# Nano-RS485_RJ45-GW-v1_7.net
KiCad netlist of a schematic drawn in EAGLE
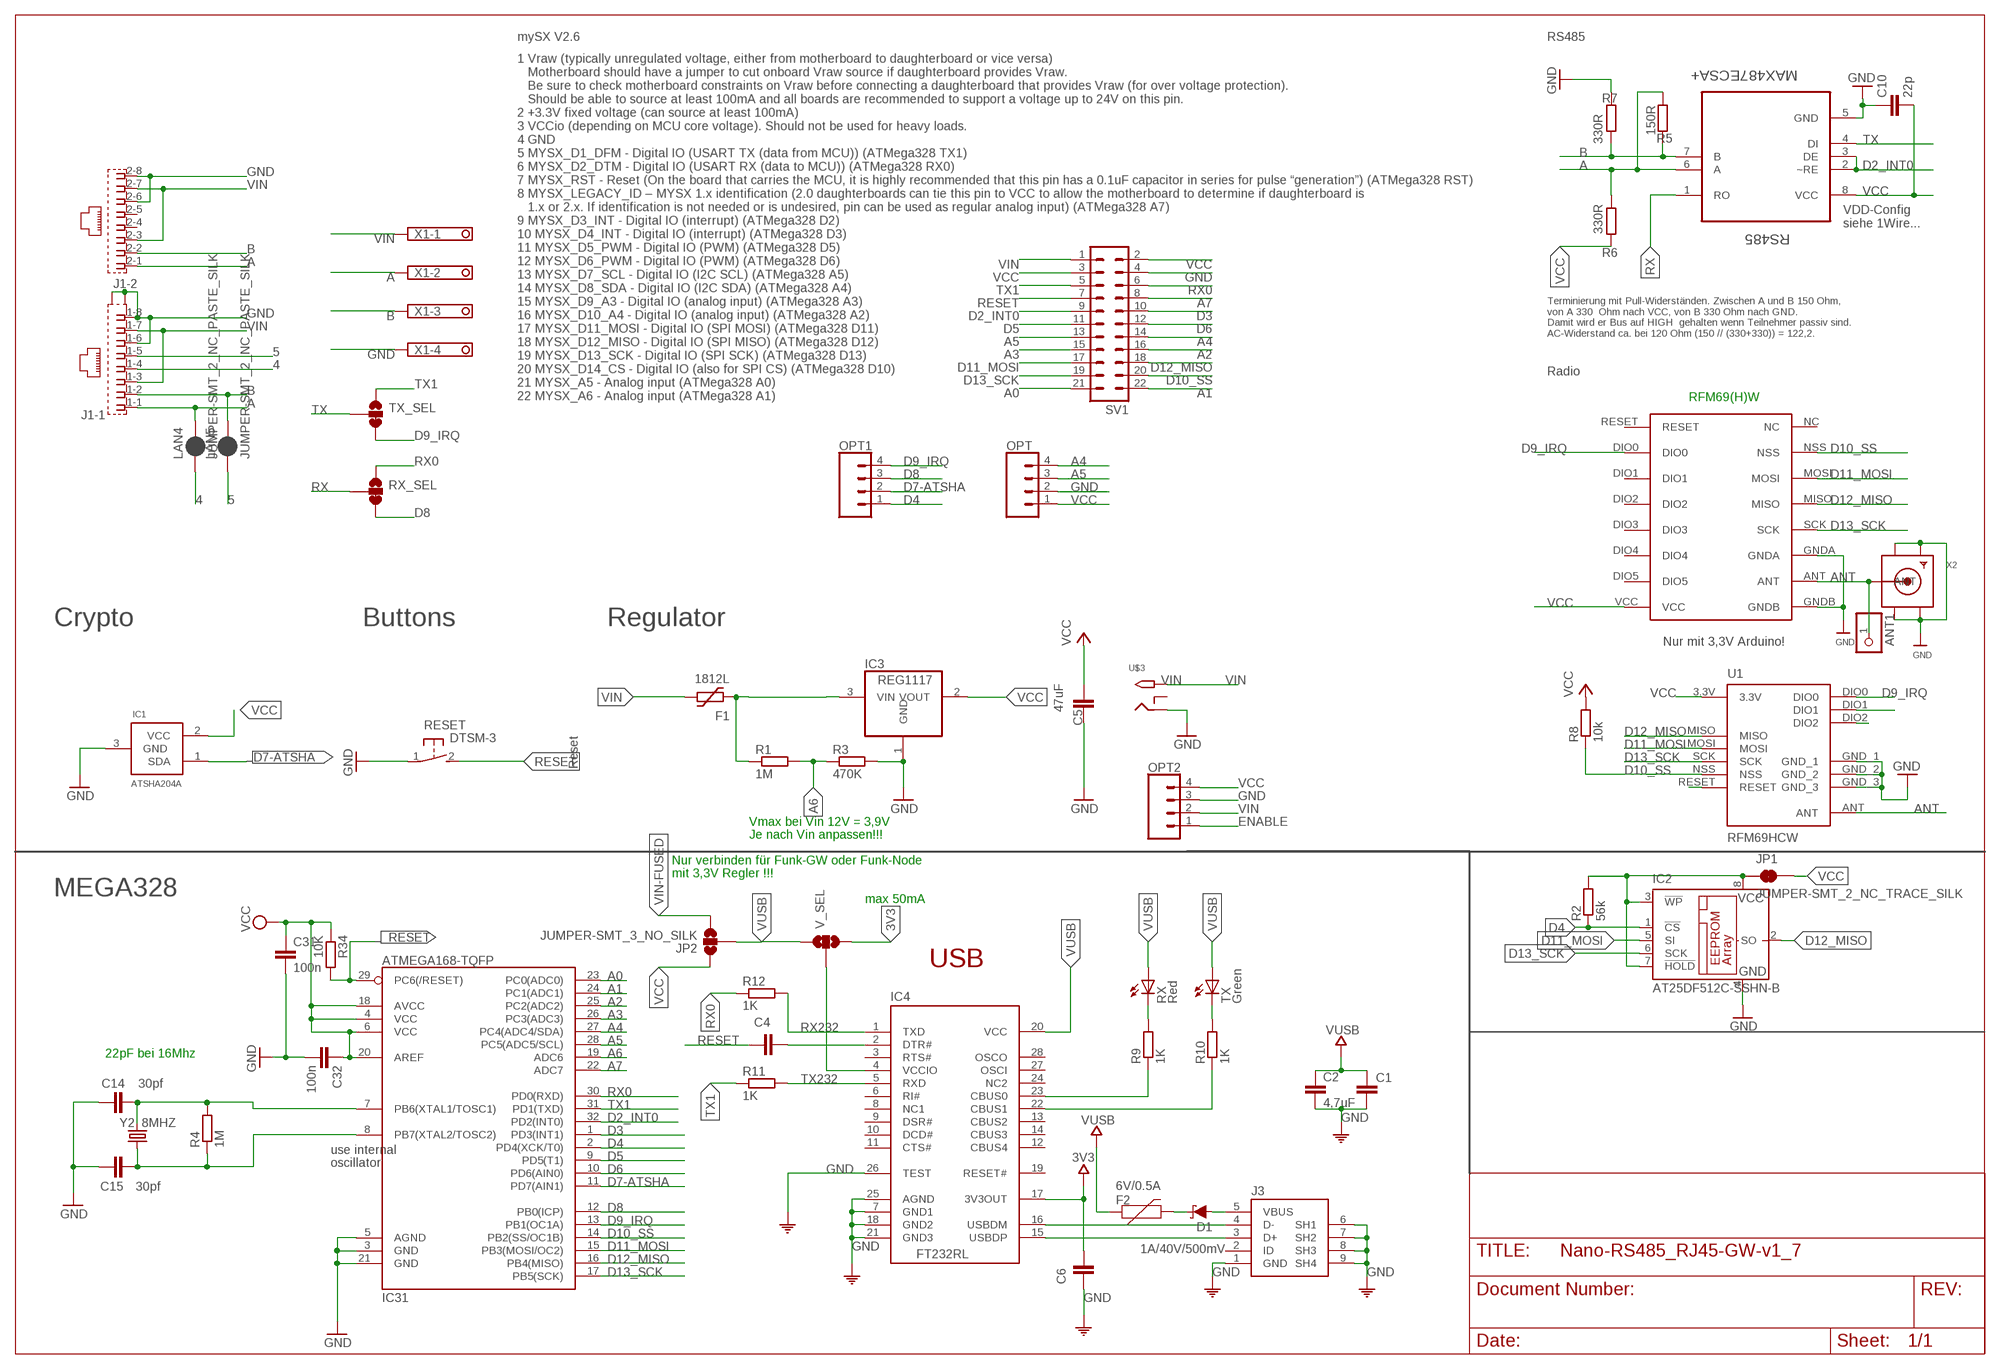
[diagram p0: schematic, sheet 1]

(export (version "E")
  (design (tool "Eeschema 10.0.6"))
  (components
    (comp (ref "ANT1")
      (value "PINHD-1X1")
      (footprint "eagle-import:1X01")
      (libsource (lib "eagle-import") (part "PINHD-1X1"))
    )
    (comp (ref "C1")
      (value "100nF")
      (footprint "eagle-import:C0805")
      (libsource (lib "eagle-import") (part "resistor@1_C-EUC0805"))
    )
    (comp (ref "C2")
      (value "4,7uF")
      (footprint "eagle-import:C1206")
      (libsource (lib "eagle-import") (part "resistor@1_C-EUC1206"))
    )
    (comp (ref "C4")
      (value "100nF")
      (footprint "eagle-import:C0805")
      (libsource (lib "eagle-import") (part "resistor@1_C-EUC0805"))
    )
    (comp (ref "C5")
      (value "47uF")
      (footprint "eagle-import:C1206")
      (libsource (lib "eagle-import") (part "resistor@1_C-EUC1206"))
    )
    (comp (ref "C6")
      (value "100nF")
      (footprint "eagle-import:C0805")
      (libsource (lib "eagle-import") (part "resistor@1_C-EUC0805"))
    )
    (comp (ref "C10")
      (value "22p")
      (footprint "eagle-import:C0805")
      (libsource (lib "eagle-import") (part "C-EUC0805"))
    )
    (comp (ref "C14")
      (value "30pf")
      (footprint "eagle-import:0805")
      (libsource (lib "eagle-import") (part "CAP0805"))
    )
    (comp (ref "C15")
      (value "30pf")
      (footprint "eagle-import:0805")
      (libsource (lib "eagle-import") (part "CAP0805"))
    )
    (comp (ref "C31")
      (value "100n")
      (footprint "eagle-import:C0805")
      (libsource (lib "eagle-import") (part "C-EUC0805"))
    )
    (comp (ref "C32")
      (value "100n")
      (footprint "eagle-import:C0805")
      (libsource (lib "eagle-import") (part "C-EUC0805"))
    )
    (comp (ref "D1")
      (value "1A/40V/500mV")
      (footprint "eagle-import:SMA-DIODE")
      (libsource (lib "eagle-import") (part "DIODE-SCHOTTKY-SS14"))
    )
    (comp (ref "F1")
      (value "1812L")
      (footprint "eagle-import:1812L")
      (libsource (lib "eagle-import") (part "1812L"))
    )
    (comp (ref "F2")
      (value "6V/0.5A")
      (footprint "eagle-import:1206")
      (libsource (lib "eagle-import") (part "PPTC_HALF-AMP"))
    )
    (comp (ref "IC1")
      (value "ATSHA204A")
      (footprint "eagle-import:SOT23")
      (libsource (lib "eagle-import") (part "ATSHA204A"))
    )
    (comp (ref "IC2")
      (value "AT25DF512C-SSHN-B")
      (footprint "eagle-import:SO-08")
      (fields (field (name "MF") "MICROCHIP") (field (name "MPN") "25AA080/SN"))
      (libsource (lib "eagle-import") (part "25SNAA080"))
    )
    (comp (ref "IC3")
      (value "REG1117")
      (footprint "eagle-import:SOT223")
      (libsource (lib "eagle-import") (part "REG1117"))
    )
    (comp (ref "IC4")
      (value "FT232RL")
      (footprint "eagle-import:SSOP28")
      (libsource (lib "eagle-import") (part "0226_FT232RL"))
    )
    (comp (ref "IC31")
      (value "ATMEGA168-TQFP")
      (footprint "eagle-import:TQFP32-08")
      (libsource (lib "eagle-import") (part "ATMEGA168-TQFP"))
    )
    (comp (ref "J1")
      (value "RJ45_2X_NARROW_SHILDPINS_NOCASE")
      (footprint "eagle-import:RJ45_2X_NARROW_SHILDPINS_NOCASE")
      (libsource (lib "eagle-import") (part "RJ45_2X_NARROW_SHILDPINS_NOCASE"))
    )
    (comp (ref "J3")
      (value "0219_14850")
      (footprint "eagle-import:USB-MINI-B_2")
      (fields (field (name "PART_NUMBER") "14850"))
      (libsource (lib "eagle-import") (part "0219_14850"))
    )
    (comp (ref "JP1")
      (value "JUMPER-SMT_2_NC_TRACE_SILK")
      (footprint "eagle-import:SMT-JUMPER_2_NC_TRACE_SILK")
      (libsource (lib "eagle-import") (part "JUMPER-SMT_2_NC_TRACE_SILK"))
    )
    (comp (ref "JP2")
      (value "JUMPER-SMT_3_NO_SILK")
      (footprint "eagle-import:SMT-JUMPER_3_NO_SILK")
      (libsource (lib "eagle-import") (part "JUMPER-SMT_3_NO_SILK"))
    )
    (comp (ref "LAN4")
      (value "JUMPER-SMT_2_NC_PASTE_SILK")
      (footprint "eagle-import:SMT-JUMPER_2_NC_PASTE_SILK")
      (libsource (lib "eagle-import") (part "JUMPER-SMT_2_NC_PASTE_SILK"))
    )
    (comp (ref "LAN5")
      (value "JUMPER-SMT_2_NC_PASTE_SILK")
      (footprint "eagle-import:SMT-JUMPER_2_NC_PASTE_SILK")
      (libsource (lib "eagle-import") (part "JUMPER-SMT_2_NC_PASTE_SILK"))
    )
    (comp (ref "OPT")
      (value "CONN_04")
      (footprint "eagle-import:1X04")
      (libsource (lib "eagle-import") (part "CONN_04"))
    )
    (comp (ref "OPT1")
      (value "CONN_04")
      (footprint "eagle-import:1X04")
      (libsource (lib "eagle-import") (part "CONN_04"))
    )
    (comp (ref "OPT2")
      (value "CONN_04")
      (footprint "eagle-import:1X04")
      (libsource (lib "eagle-import") (part "CONN_04"))
    )
    (comp (ref "R1")
      (value "1M")
      (footprint "eagle-import:M0805")
      (libsource (lib "eagle-import") (part "R-EU_M0805"))
    )
    (comp (ref "R2")
      (value "56k")
      (footprint "eagle-import:M0805")
      (libsource (lib "eagle-import") (part "resistor_R-EU_M0805"))
    )
    (comp (ref "R3")
      (value "470K")
      (footprint "eagle-import:R0805")
      (libsource (lib "eagle-import") (part "R-EU_R0805"))
    )
    (comp (ref "R4")
      (value "1M")
      (footprint "eagle-import:M0805")
      (libsource (lib "eagle-import") (part "R-EU_M0805"))
    )
    (comp (ref "R5")
      (value "150R")
      (footprint "eagle-import:R0805")
      (libsource (lib "eagle-import") (part "R-EU_R0805"))
    )
    (comp (ref "R6")
      (value "330R")
      (footprint "eagle-import:R0805")
      (libsource (lib "eagle-import") (part "R-EU_R0805"))
    )
    (comp (ref "R7")
      (value "330R")
      (footprint "eagle-import:R0805")
      (libsource (lib "eagle-import") (part "R-EU_R0805"))
    )
    (comp (ref "R8")
      (value "10k")
      (footprint "eagle-import:M0805")
      (libsource (lib "eagle-import") (part "R-EU_M0805"))
    )
    (comp (ref "R9")
      (value "1K")
      (footprint "eagle-import:R0805")
      (libsource (lib "eagle-import") (part "resistor@1_R-EU_R0805"))
    )
    (comp (ref "R10")
      (value "1K")
      (footprint "eagle-import:R0805")
      (libsource (lib "eagle-import") (part "resistor@1_R-EU_R0805"))
    )
    (comp (ref "R11")
      (value "1K")
      (footprint "eagle-import:R0805")
      (libsource (lib "eagle-import") (part "resistor@1_R-EU_R0805"))
    )
    (comp (ref "R12")
      (value "1K")
      (footprint "eagle-import:R0805")
      (libsource (lib "eagle-import") (part "resistor@1_R-EU_R0805"))
    )
    (comp (ref "R34")
      (value "10K")
      (footprint "eagle-import:R0805")
      (libsource (lib "eagle-import") (part "R-EU_R0805"))
    )
    (comp (ref "RESET")
      (value "DTSM-3")
      (footprint "eagle-import:DTSM-3")
      (libsource (lib "eagle-import") (part "DTSM-3"))
    )
    (comp (ref "RFM69W")
      (value "RFM69HW")
      (footprint "eagle-import:RFM")
      (libsource (lib "eagle-import") (part "RFM69HW"))
    )
    (comp (ref "RS485")
      (value "MAX487ECSA+")
      (footprint "eagle-import:SOIC127P600X175-8N")
      (libsource (lib "eagle-import") (part "MAX487ECSA+"))
    )
    (comp (ref "RX")
      (value "Red")
      (footprint "eagle-import:CHIPLED_0805")
      (fields (field (name "PART_NUMBER") "KTP-2012SURCK"))
      (libsource (lib "eagle-import") (part "0181_KTP-2012SURCK"))
    )
    (comp (ref "RX_SEL")
      (value "JUMPER-SMT_3_1-NC_TRACE_SILK")
      (footprint "eagle-import:SMT-JUMPER_3_1-NC_TRACE_SILK")
      (libsource (lib "eagle-import") (part "JUMPER-SMT_3_1-NC_TRACE_SILK"))
    )
    (comp (ref "SV1")
      (value "MA11-2")
      (footprint "eagle-import:MA11-2")
      (libsource (lib "eagle-import") (part "MA11-2"))
    )
    (comp (ref "TX")
      (value "Green")
      (footprint "eagle-import:CHIPLED_0805")
      (fields (field (name "PART_NUMBER") "KPT-2012SGC"))
      (libsource (lib "eagle-import") (part "0043_KPT-2012SGC"))
    )
    (comp (ref "TX_SEL")
      (value "JUMPER-SMT_3_1-NC_TRACE_SILK")
      (footprint "eagle-import:SMT-JUMPER_3_1-NC_TRACE_SILK")
      (libsource (lib "eagle-import") (part "JUMPER-SMT_3_1-NC_TRACE_SILK"))
    )
    (comp (ref "U$3")
      (value "2.1MMJACKTHM")
      (footprint "eagle-import:PJ-102A")
      (libsource (lib "eagle-import") (part "2.1MMJACKTHM"))
    )
    (comp (ref "U1")
      (value "RFM69HCW")
      (footprint "eagle-import:RFM69HCW-XXXS2")
      (libsource (lib "eagle-import") (part "RFM69HCW"))
    )
    (comp (ref "V_SEL")
      (value "JUMPER-SMT_3_NO_SILK")
      (footprint "eagle-import:SMT-JUMPER_3_NO_SILK")
      (libsource (lib "eagle-import") (part "JUMPER-SMT_3_NO_SILK"))
    )
    (comp (ref "X1")
      (value "1751264")
      (footprint "eagle-import:1751264")
      (libsource (lib "eagle-import") (part "1751264"))
    )
    (comp (ref "X2")
      (value "SMACONNECTOR_EDGE")
      (footprint "eagle-import:SMA_EDGELAUNCH")
      (libsource (lib "eagle-import") (part "SMACONNECTOR_EDGE"))
    )
    (comp (ref "Y2")
      (value "8MHZ")
      (footprint "eagle-import:CRYSTAL-TXC-7A")
      (libsource (lib "eagle-import") (part "CRYSTALTXC-7A"))
    )
  )
  (nets
    (net (code "1") (name "/4") (class "Default")
      (node (ref "J1") (pin "1-4") (pinfunction "4_1-4") (pintype "passive"))
      (node (ref "LAN4") (pin "1") (pinfunction "1_1") (pintype "passive"))
    )
    (net (code "2") (name "/5") (class "Default")
      (node (ref "J1") (pin "1-5") (pinfunction "5_1-5") (pintype "passive"))
      (node (ref "LAN5") (pin "1") (pinfunction "1_1") (pintype "passive"))
    )
    (net (code "3") (name "/A") (class "Default")
      (node (ref "J1") (pin "1-1") (pinfunction "1_1-1") (pintype "passive"))
      (node (ref "J1") (pin "2-1") (pinfunction "1_2-1") (pintype "passive"))
      (node (ref "LAN4") (pin "2") (pinfunction "2_2") (pintype "passive"))
      (node (ref "R5") (pin "1") (pinfunction "1_1") (pintype "passive"))
      (node (ref "R6") (pin "2") (pinfunction "2_2") (pintype "passive"))
      (node (ref "RS485") (pin "6") (pinfunction "A_6") (pintype "bidirectional"))
      (node (ref "X1") (pin "2") (pinfunction "K_2") (pintype "passive"))
    )
    (net (code "4") (name "/A0") (class "Default")
      (node (ref "IC31") (pin "23") (pinfunction "PC0(ADC0)_23") (pintype "bidirectional"))
      (node (ref "SV1") (pin "21") (pinfunction "21_21") (pintype "passive"))
    )
    (net (code "5") (name "/A1") (class "Default")
      (node (ref "IC31") (pin "24") (pinfunction "PC1(ADC1)_24") (pintype "bidirectional"))
      (node (ref "SV1") (pin "22") (pinfunction "22_22") (pintype "passive"))
    )
    (net (code "6") (name "/A2") (class "Default")
      (node (ref "IC31") (pin "25") (pinfunction "PC2(ADC2)_25") (pintype "bidirectional"))
      (node (ref "SV1") (pin "16") (pinfunction "16_16") (pintype "passive"))
    )
    (net (code "7") (name "/A3") (class "Default")
      (node (ref "IC31") (pin "26") (pinfunction "PC3(ADC3)_26") (pintype "bidirectional"))
      (node (ref "SV1") (pin "15") (pinfunction "15_15") (pintype "passive"))
    )
    (net (code "8") (name "/A4") (class "Default")
      (node (ref "IC31") (pin "27") (pinfunction "PC4(ADC4/SDA)_27") (pintype "bidirectional"))
      (node (ref "OPT") (pin "4") (pinfunction "4_4") (pintype "passive"))
      (node (ref "SV1") (pin "14") (pinfunction "14_14") (pintype "passive"))
    )
    (net (code "9") (name "/A5") (class "Default")
      (node (ref "IC31") (pin "28") (pinfunction "PC5(ADC5/SCL)_28") (pintype "bidirectional"))
      (node (ref "OPT") (pin "3") (pinfunction "3_3") (pintype "passive"))
      (node (ref "SV1") (pin "13") (pinfunction "13_13") (pintype "passive"))
    )
    (net (code "10") (name "/A7") (class "Default")
      (node (ref "IC31") (pin "22") (pinfunction "ADC7_22") (pintype "bidirectional"))
      (node (ref "SV1") (pin "8") (pinfunction "8_8") (pintype "passive"))
    )
    (net (code "11") (name "/ANT") (class "Default")
      (node (ref "ANT1") (pin "1") (pinfunction "1_1") (pintype "passive"))
      (node (ref "RFM69W") (pin "ANT") (pinfunction "ANT_ANT") (pintype "bidirectional"))
      (node (ref "U1") (pin "ANT") (pinfunction "ANT_ANT") (pintype "passive"))
      (node (ref "X2") (pin "P") (pinfunction "ANT_P") (pintype "bidirectional"))
    )
    (net (code "12") (name "/B") (class "Default")
      (node (ref "J1") (pin "1-2") (pinfunction "2_1-2") (pintype "passive"))
      (node (ref "J1") (pin "2-2") (pinfunction "2_2-2") (pintype "passive"))
      (node (ref "LAN5") (pin "2") (pinfunction "2_2") (pintype "passive"))
      (node (ref "R5") (pin "2") (pinfunction "2_2") (pintype "passive"))
      (node (ref "R7") (pin "1") (pinfunction "1_1") (pintype "passive"))
      (node (ref "RS485") (pin "7") (pinfunction "B_7") (pintype "bidirectional"))
      (node (ref "X1") (pin "3") (pinfunction "K_3") (pintype "passive"))
    )
    (net (code "13") (name "/D2_INT0") (class "Default")
      (node (ref "IC31") (pin "32") (pinfunction "PD2(INT0)_32") (pintype "bidirectional"))
      (node (ref "RS485") (pin "2") (pinfunction "~{RE}_2") (pintype "input"))
      (node (ref "RS485") (pin "3") (pinfunction "DE_3") (pintype "input"))
      (node (ref "SV1") (pin "9") (pinfunction "9_9") (pintype "passive"))
    )
    (net (code "14") (name "/D3") (class "Default")
      (node (ref "IC31") (pin "1") (pinfunction "PD3(INT1)_1") (pintype "bidirectional"))
      (node (ref "SV1") (pin "10") (pinfunction "10_10") (pintype "passive"))
    )
    (net (code "15") (name "/D5") (class "Default")
      (node (ref "IC31") (pin "9") (pinfunction "PD5(T1)_9") (pintype "bidirectional"))
      (node (ref "SV1") (pin "11") (pinfunction "11_11") (pintype "passive"))
    )
    (net (code "16") (name "/D6") (class "Default")
      (node (ref "IC31") (pin "10") (pinfunction "PD6(AIN0)_10") (pintype "bidirectional"))
      (node (ref "SV1") (pin "12") (pinfunction "12_12") (pintype "passive"))
    )
    (net (code "17") (name "/D7-ATSHA") (class "Default")
      (node (ref "IC1") (pin "1") (pinfunction "SDA_1") (pintype "bidirectional"))
      (node (ref "IC31") (pin "11") (pinfunction "PD7(AIN1)_11") (pintype "bidirectional"))
      (node (ref "OPT1") (pin "2") (pinfunction "2_2") (pintype "passive"))
    )
    (net (code "18") (name "/D8") (class "Default")
      (node (ref "IC31") (pin "12") (pinfunction "PB0(ICP)_12") (pintype "bidirectional"))
      (node (ref "OPT1") (pin "3") (pinfunction "3_3") (pintype "passive"))
      (node (ref "RX_SEL") (pin "3") (pinfunction "3_3") (pintype "passive"))
    )
    (net (code "19") (name "/D9_IRQ") (class "Default")
      (node (ref "IC31") (pin "13") (pinfunction "PB1(OC1A)_13") (pintype "bidirectional"))
      (node (ref "OPT1") (pin "4") (pinfunction "4_4") (pintype "passive"))
      (node (ref "RFM69W") (pin "DIO0") (pinfunction "DIO0_DIO0") (pintype "bidirectional"))
      (node (ref "TX_SEL") (pin "3") (pinfunction "3_3") (pintype "passive"))
      (node (ref "U1") (pin "DIO0") (pinfunction "DIO0_DIO0") (pintype "bidirectional"))
    )
    (net (code "20") (name "/D10_SS") (class "Default")
      (node (ref "IC31") (pin "14") (pinfunction "PB2(SS/OC1B)_14") (pintype "bidirectional"))
      (node (ref "R8") (pin "1") (pinfunction "1_1") (pintype "passive"))
      (node (ref "RFM69W") (pin "NSS") (pinfunction "NSS_NSS") (pintype "bidirectional"))
      (node (ref "SV1") (pin "20") (pinfunction "20_20") (pintype "passive"))
      (node (ref "U1") (pin "NSS") (pinfunction "NSS_NSS") (pintype "input"))
    )
    (net (code "21") (name "/ENABLE") (class "Default")
      (node (ref "OPT2") (pin "1") (pinfunction "1_1") (pintype "passive"))
    )
    (net (code "22") (name "/RX232") (class "Default")
      (node (ref "IC4") (pin "1") (pinfunction "TXD_1") (pintype "output"))
      (node (ref "R12") (pin "2") (pinfunction "2_2") (pintype "passive"))
    )
    (net (code "23") (name "/TX") (class "Default")
      (node (ref "RS485") (pin "4") (pinfunction "DI_4") (pintype "input"))
      (node (ref "TX_SEL") (pin "2") (pinfunction "2_2") (pintype "passive"))
    )
    (net (code "24") (name "/TX232") (class "Default")
      (node (ref "IC4") (pin "5") (pinfunction "RXD_5") (pintype "input"))
      (node (ref "R11") (pin "2") (pinfunction "2_2") (pintype "passive"))
    )
    (net (code "25") (name "3V3") (class "Default")
      (node (ref "C6") (pin "2") (pinfunction "2_2") (pintype "passive"))
      (node (ref "IC4") (pin "17") (pinfunction "3V3OUT_17") (pintype "power_in"))
      (node (ref "V_SEL") (pin "3") (pinfunction "3_3") (pintype "passive"))
    )
    (net (code "26") (name "A6") (class "Default")
      (node (ref "IC31") (pin "19") (pinfunction "ADC6_19") (pintype "bidirectional"))
      (node (ref "R1") (pin "2") (pinfunction "2_2") (pintype "passive"))
      (node (ref "R3") (pin "1") (pinfunction "1_1") (pintype "passive"))
    )
    (net (code "27") (name "COM") (class "Default")
      (node (ref "C1") (pin "2") (pinfunction "2_2") (pintype "passive"))
      (node (ref "C10") (pin "1") (pinfunction "1_1") (pintype "passive"))
      (node (ref "C14") (pin "1") (pinfunction "1_1") (pintype "passive"))
      (node (ref "C15") (pin "1") (pinfunction "1_1") (pintype "passive"))
      (node (ref "C2") (pin "2") (pinfunction "2_2") (pintype "passive"))
      (node (ref "C31") (pin "2") (pinfunction "2_2") (pintype "passive"))
      (node (ref "C32") (pin "2") (pinfunction "2_2") (pintype "passive"))
      (node (ref "C5") (pin "1") (pinfunction "1_1") (pintype "passive"))
      (node (ref "C6") (pin "1") (pinfunction "1_1") (pintype "passive"))
      (node (ref "IC1") (pin "3") (pinfunction "GND_3") (pintype "bidirectional"))
      (node (ref "IC2") (pin "4") (pinfunction "GND_4") (pintype "power_in"))
      (node (ref "IC3") (pin "1") (pinfunction "GND_1") (pintype "power_in"))
      (node (ref "IC31") (pin "21") (pinfunction "GND_21") (pintype "bidirectional"))
      (node (ref "IC31") (pin "3") (pinfunction "GND_3") (pintype "bidirectional"))
      (node (ref "IC31") (pin "5") (pinfunction "AGND_5") (pintype "bidirectional"))
      (node (ref "IC4") (pin "18") (pinfunction "GND2_18") (pintype "power_in"))
      (node (ref "IC4") (pin "21") (pinfunction "GND3_21") (pintype "power_in"))
      (node (ref "IC4") (pin "25") (pinfunction "AGND_25") (pintype "power_in"))
      (node (ref "IC4") (pin "26") (pinfunction "TEST_26") (pintype "bidirectional"))
      (node (ref "IC4") (pin "7") (pinfunction "GND1_7") (pintype "power_in"))
      (node (ref "J1") (pin "1-6") (pinfunction "6_1-6") (pintype "passive"))
      (node (ref "J1") (pin "1-8") (pinfunction "8_1-8") (pintype "passive"))
      (node (ref "J1") (pin "2-6") (pinfunction "6_2-6") (pintype "passive"))
      (node (ref "J1") (pin "2-8") (pinfunction "8_2-8") (pintype "passive"))
      (node (ref "J1") (pin "G1") (pinfunction "S1_G1") (pintype "passive"))
      (node (ref "J1") (pin "G3") (pinfunction "S2_G3") (pintype "passive"))
      (node (ref "J3") (pin "1") (pinfunction "GND_1") (pintype "passive"))
      (node (ref "J3") (pin "6") (pinfunction "SH1_6") (pintype "passive"))
      (node (ref "J3") (pin "7") (pinfunction "SH2_7") (pintype "passive"))
      (node (ref "J3") (pin "8") (pinfunction "SH3_8") (pintype "passive"))
      (node (ref "J3") (pin "9") (pinfunction "SH4_9") (pintype "passive"))
      (node (ref "OPT") (pin "2") (pinfunction "2_2") (pintype "passive"))
      (node (ref "OPT2") (pin "3") (pinfunction "3_3") (pintype "passive"))
      (node (ref "R3") (pin "2") (pinfunction "2_2") (pintype "passive"))
      (node (ref "R7") (pin "2") (pinfunction "2_2") (pintype "passive"))
      (node (ref "RESET") (pin "1") (pinfunction "1_1") (pintype "passive"))
      (node (ref "RFM69W") (pin "GNDA") (pinfunction "GNDA_GNDA") (pintype "bidirectional"))
      (node (ref "RFM69W") (pin "GNDB") (pinfunction "GNDB_GNDB") (pintype "bidirectional"))
      (node (ref "RS485") (pin "5") (pinfunction "GND_5") (pintype "passive"))
      (node (ref "SV1") (pin "4") (pinfunction "4_4") (pintype "passive"))
      (node (ref "U$3") (pin "RING") (pinfunction "RING_RING") (pintype "bidirectional"))
      (node (ref "U1") (pin "GND_1") (pinfunction "GND_1_GND_1") (pintype "power_in"))
      (node (ref "U1") (pin "GND_2") (pinfunction "GND_2_GND_2") (pintype "power_in"))
      (node (ref "U1") (pin "GND_3") (pinfunction "GND_3_GND_3") (pintype "power_in"))
      (node (ref "X1") (pin "4") (pinfunction "K_4") (pintype "passive"))
      (node (ref "X2") (pin "GND@1") (pinfunction "GND4_GND@1") (pintype "power_in"))
      (node (ref "X2") (pin "GND@2") (pinfunction "GND3_GND@2") (pintype "power_in"))
      (node (ref "X2") (pin "GND@3") (pinfunction "GND2_GND@3") (pintype "power_in"))
      (node (ref "X2") (pin "GND@4") (pinfunction "GND1_GND@4") (pintype "power_in"))
    )
    (net (code "28") (name "D4") (class "Default")
      (node (ref "IC2") (pin "1") (pinfunction "~{CS}_1") (pintype "input"))
      (node (ref "IC31") (pin "2") (pinfunction "PD4(XCK/T0)_2") (pintype "bidirectional"))
      (node (ref "OPT1") (pin "1") (pinfunction "1_1") (pintype "passive"))
      (node (ref "R2") (pin "1") (pinfunction "1_1") (pintype "passive"))
    )
    (net (code "29") (name "D11_MOSI") (class "Default")
      (node (ref "IC2") (pin "5") (pinfunction "SI_5") (pintype "input"))
      (node (ref "IC31") (pin "15") (pinfunction "PB3(MOSI/OC2)_15") (pintype "bidirectional"))
      (node (ref "RFM69W") (pin "MOSI") (pinfunction "MOSI_MOSI") (pintype "bidirectional"))
      (node (ref "SV1") (pin "17") (pinfunction "17_17") (pintype "passive"))
      (node (ref "U1") (pin "MOSI") (pinfunction "MOSI_MOSI") (pintype "input"))
    )
    (net (code "30") (name "D12_MISO") (class "Default")
      (node (ref "IC2") (pin "2") (pinfunction "SO_2") (pintype "bidirectional"))
      (node (ref "IC31") (pin "16") (pinfunction "PB4(MISO)_16") (pintype "bidirectional"))
      (node (ref "RFM69W") (pin "MISO") (pinfunction "MISO_MISO") (pintype "bidirectional"))
      (node (ref "SV1") (pin "18") (pinfunction "18_18") (pintype "passive"))
      (node (ref "U1") (pin "MISO") (pinfunction "MISO_MISO") (pintype "bidirectional"))
    )
    (net (code "31") (name "D13_SCK") (class "Default")
      (node (ref "IC2") (pin "6") (pinfunction "SCK_6") (pintype "input"))
      (node (ref "IC31") (pin "17") (pinfunction "PB5(SCK)_17") (pintype "bidirectional"))
      (node (ref "RFM69W") (pin "SCK") (pinfunction "SCK_SCK") (pintype "bidirectional"))
      (node (ref "SV1") (pin "19") (pinfunction "19_19") (pintype "passive"))
      (node (ref "U1") (pin "SCK") (pinfunction "SCK_SCK") (pintype "input"))
    )
    (net (code "32") (name "Net-(D1-PadC)") (class "Default")
      (node (ref "D1") (pin "C") (pinfunction "C_C") (pintype "passive"))
      (node (ref "F2") (pin "2") (pinfunction "2_2") (pintype "bidirectional"))
    )
    (net (code "33") (name "Net-(IC2-VCC)") (class "Default")
      (node (ref "IC2") (pin "3") (pinfunction "~{WP}_3") (pintype "input"))
      (node (ref "IC2") (pin "7") (pinfunction "~{HOLD}_7") (pintype "input"))
      (node (ref "IC2") (pin "8") (pinfunction "VCC_8") (pintype "power_in"))
      (node (ref "JP1") (pin "1") (pinfunction "1_1") (pintype "passive"))
      (node (ref "R2") (pin "2") (pinfunction "2_2") (pintype "passive"))
    )
    (net (code "34") (name "Net-(IC4-CBUS0)") (class "Default")
      (node (ref "IC4") (pin "23") (pinfunction "CBUS0_23") (pintype "bidirectional"))
      (node (ref "R9") (pin "1") (pinfunction "1_1") (pintype "passive"))
    )
    (net (code "35") (name "Net-(IC4-CBUS1)") (class "Default")
      (node (ref "IC4") (pin "22") (pinfunction "CBUS1_22") (pintype "bidirectional"))
      (node (ref "R10") (pin "1") (pinfunction "1_1") (pintype "passive"))
    )
    (net (code "36") (name "Net-(IC4-DTR#)") (class "Default")
      (node (ref "C4") (pin "2") (pinfunction "2_2") (pintype "passive"))
      (node (ref "IC4") (pin "2") (pinfunction "DTR#_2") (pintype "output"))
    )
    (net (code "37") (name "Net-(IC4-USBDM)") (class "Default")
      (node (ref "IC4") (pin "16") (pinfunction "USBDM_16") (pintype "bidirectional"))
      (node (ref "J3") (pin "4") (pinfunction "D-_4") (pintype "bidirectional"))
    )
    (net (code "38") (name "Net-(IC4-USBDP)") (class "Default")
      (node (ref "IC4") (pin "15") (pinfunction "USBDP_15") (pintype "bidirectional"))
      (node (ref "J3") (pin "3") (pinfunction "D+_3") (pintype "bidirectional"))
    )
    (net (code "39") (name "Net-(IC4-VCCIO)") (class "Default")
      (node (ref "IC4") (pin "4") (pinfunction "VCCIO_4") (pintype "power_in"))
      (node (ref "V_SEL") (pin "2") (pinfunction "2_2") (pintype "passive"))
    )
    (net (code "40") (name "Net-(IC31-PB6(XTAL1{slash}TOSC1))") (class "Default")
      (node (ref "C14") (pin "2") (pinfunction "2_2") (pintype "passive"))
      (node (ref "IC31") (pin "7") (pinfunction "PB6(XTAL1/TOSC1)_7") (pintype "bidirectional"))
      (node (ref "R4") (pin "2") (pinfunction "2_2") (pintype "passive"))
      (node (ref "Y2") (pin "P$2") (pinfunction "2_P$2") (pintype "passive"))
    )
    (net (code "41") (name "Net-(IC31-PB7(XTAL2{slash}TOSC2))") (class "Default")
      (node (ref "C15") (pin "2") (pinfunction "2_2") (pintype "passive"))
      (node (ref "IC31") (pin "8") (pinfunction "PB7(XTAL2/TOSC2)_8") (pintype "bidirectional"))
      (node (ref "R4") (pin "1") (pinfunction "1_1") (pintype "passive"))
      (node (ref "Y2") (pin "P$1") (pinfunction "1_P$1") (pintype "passive"))
    )
    (net (code "42") (name "Net-(J3-VBUS)") (class "Default")
      (node (ref "D1") (pin "A") (pinfunction "A_A") (pintype "passive"))
      (node (ref "J3") (pin "5") (pinfunction "VBUS_5") (pintype "power_in"))
    )
    (net (code "43") (name "Net-(R9-Pad2)") (class "Default")
      (node (ref "R9") (pin "2") (pinfunction "2_2") (pintype "passive"))
      (node (ref "RX") (pin "C") (pinfunction "C_C") (pintype "passive"))
    )
    (net (code "44") (name "Net-(R10-Pad2)") (class "Default")
      (node (ref "R10") (pin "2") (pinfunction "2_2") (pintype "passive"))
      (node (ref "TX") (pin "C") (pinfunction "C_C") (pintype "passive"))
    )
    (net (code "45") (name "RESET") (class "Default")
      (node (ref "C4") (pin "1") (pinfunction "1_1") (pintype "passive"))
      (node (ref "IC31") (pin "29") (pinfunction "PC6(/RESET)_29") (pintype "bidirectional"))
      (node (ref "R34") (pin "2") (pinfunction "2_2") (pintype "passive"))
      (node (ref "RESET") (pin "2") (pinfunction "2_2") (pintype "passive"))
      (node (ref "SV1") (pin "7") (pinfunction "7_7") (pintype "passive"))
    )
    (net (code "46") (name "RX") (class "Default")
      (node (ref "RS485") (pin "1") (pinfunction "RO_1") (pintype "output"))
      (node (ref "RX_SEL") (pin "2") (pinfunction "2_2") (pintype "passive"))
    )
    (net (code "47") (name "RX0") (class "Default")
      (node (ref "IC31") (pin "30") (pinfunction "PD0(RXD)_30") (pintype "bidirectional"))
      (node (ref "R12") (pin "1") (pinfunction "1_1") (pintype "passive"))
      (node (ref "RX_SEL") (pin "1") (pinfunction "1_1") (pintype "passive"))
      (node (ref "SV1") (pin "6") (pinfunction "6_6") (pintype "passive"))
    )
    (net (code "48") (name "TX1") (class "Default")
      (node (ref "IC31") (pin "31") (pinfunction "PD1(TXD)_31") (pintype "bidirectional"))
      (node (ref "R11") (pin "1") (pinfunction "1_1") (pintype "passive"))
      (node (ref "SV1") (pin "5") (pinfunction "5_5") (pintype "passive"))
      (node (ref "TX_SEL") (pin "1") (pinfunction "1_1") (pintype "passive"))
    )
    (net (code "49") (name "VCC") (class "Default")
      (node (ref "C10") (pin "2") (pinfunction "2_2") (pintype "passive"))
      (node (ref "C31") (pin "1") (pinfunction "1_1") (pintype "passive"))
      (node (ref "C32") (pin "1") (pinfunction "1_1") (pintype "passive"))
      (node (ref "C5") (pin "2") (pinfunction "2_2") (pintype "passive"))
      (node (ref "IC1") (pin "2") (pinfunction "VCC_2") (pintype "bidirectional"))
      (node (ref "IC3") (pin "2") (pinfunction "VOUT_2") (pintype "output"))
      (node (ref "IC31") (pin "18") (pinfunction "AVCC_18") (pintype "bidirectional"))
      (node (ref "IC31") (pin "20") (pinfunction "AREF_20") (pintype "bidirectional"))
      (node (ref "IC31") (pin "4") (pinfunction "VCC_4") (pintype "bidirectional"))
      (node (ref "IC31") (pin "6") (pinfunction "VCC_6") (pintype "bidirectional"))
      (node (ref "JP1") (pin "2") (pinfunction "2_2") (pintype "passive"))
      (node (ref "JP2") (pin "1") (pinfunction "1_1") (pintype "passive"))
      (node (ref "OPT") (pin "1") (pinfunction "1_1") (pintype "passive"))
      (node (ref "OPT2") (pin "4") (pinfunction "4_4") (pintype "passive"))
      (node (ref "R34") (pin "1") (pinfunction "1_1") (pintype "passive"))
      (node (ref "R6") (pin "1") (pinfunction "1_1") (pintype "passive"))
      (node (ref "R8") (pin "2") (pinfunction "2_2") (pintype "passive"))
      (node (ref "RFM69W") (pin "VCC") (pinfunction "VCC_VCC") (pintype "bidirectional"))
      (node (ref "RS485") (pin "8") (pinfunction "VCC_8") (pintype "power_in"))
      (node (ref "SV1") (pin "2") (pinfunction "2_2") (pintype "passive"))
      (node (ref "SV1") (pin "3") (pinfunction "3_3") (pintype "passive"))
      (node (ref "U1") (pin "3.3V") (pinfunction "3.3V_3.3V") (pintype "power_in"))
    )
    (net (code "50") (name "VIN") (class "Default")
      (node (ref "F1") (pin "P$2") (pinfunction "2_P$2") (pintype "passive"))
      (node (ref "J1") (pin "1-3") (pinfunction "3_1-3") (pintype "passive"))
      (node (ref "J1") (pin "1-7") (pinfunction "7_1-7") (pintype "passive"))
      (node (ref "J1") (pin "2-3") (pinfunction "3_2-3") (pintype "passive"))
      (node (ref "J1") (pin "2-7") (pinfunction "7_2-7") (pintype "passive"))
      (node (ref "OPT2") (pin "2") (pinfunction "2_2") (pintype "passive"))
      (node (ref "SV1") (pin "1") (pinfunction "1_1") (pintype "passive"))
      (node (ref "U$3") (pin "TIP") (pinfunction "TIP_TIP") (pintype "bidirectional"))
      (node (ref "X1") (pin "1") (pinfunction "K_1") (pintype "passive"))
    )
    (net (code "51") (name "VIN-FUSED") (class "Default")
      (node (ref "F1") (pin "P$1") (pinfunction "1_P$1") (pintype "passive"))
      (node (ref "IC3") (pin "3") (pinfunction "VIN_3") (pintype "input"))
      (node (ref "JP2") (pin "3") (pinfunction "3_3") (pintype "passive"))
      (node (ref "R1") (pin "1") (pinfunction "1_1") (pintype "passive"))
    )
    (net (code "52") (name "VUSB") (class "Default")
      (node (ref "C1") (pin "1") (pinfunction "1_1") (pintype "passive"))
      (node (ref "C2") (pin "1") (pinfunction "1_1") (pintype "passive"))
      (node (ref "F2") (pin "1") (pinfunction "1_1") (pintype "bidirectional"))
      (node (ref "IC4") (pin "20") (pinfunction "VCC_20") (pintype "power_in"))
      (node (ref "JP2") (pin "2") (pinfunction "2_2") (pintype "passive"))
      (node (ref "RX") (pin "A") (pinfunction "A_A") (pintype "passive"))
      (node (ref "TX") (pin "A") (pinfunction "A_A") (pintype "passive"))
      (node (ref "V_SEL") (pin "1") (pinfunction "1_1") (pintype "passive"))
    )
    (net (code "53") (name "unconnected-(IC4-CBUS2-Pad13)") (class "Default")
      (node (ref "IC4") (pin "13") (pinfunction "CBUS2_13") (pintype "bidirectional"))
    )
    (net (code "54") (name "unconnected-(IC4-CBUS3-Pad14)") (class "Default")
      (node (ref "IC4") (pin "14") (pinfunction "CBUS3_14") (pintype "bidirectional"))
    )
    (net (code "55") (name "unconnected-(IC4-CBUS4-Pad12)") (class "Default")
      (node (ref "IC4") (pin "12") (pinfunction "CBUS4_12") (pintype "bidirectional"))
    )
    (net (code "56") (name "unconnected-(IC4-CTS#-Pad11)") (class "Default")
      (node (ref "IC4") (pin "11") (pinfunction "CTS#_11") (pintype "bidirectional"))
    )
    (net (code "57") (name "unconnected-(IC4-DCD#-Pad10)") (class "Default")
      (node (ref "IC4") (pin "10") (pinfunction "DCD#_10") (pintype "bidirectional"))
    )
    (net (code "58") (name "unconnected-(IC4-DSR#-Pad9)") (class "Default")
      (node (ref "IC4") (pin "9") (pinfunction "DSR#_9") (pintype "bidirectional"))
    )
    (net (code "59") (name "unconnected-(IC4-NC1-Pad8)") (class "Default")
      (node (ref "IC4") (pin "8") (pinfunction "NC1_8") (pintype "bidirectional"))
    )
    (net (code "60") (name "unconnected-(IC4-NC2-Pad24)") (class "Default")
      (node (ref "IC4") (pin "24") (pinfunction "NC2_24") (pintype "no_connect"))
    )
    (net (code "61") (name "unconnected-(IC4-OSCI-Pad27)") (class "Default")
      (node (ref "IC4") (pin "27") (pinfunction "OSCI_27") (pintype "bidirectional"))
    )
    (net (code "62") (name "unconnected-(IC4-OSCO-Pad28)") (class "Default")
      (node (ref "IC4") (pin "28") (pinfunction "OSCO_28") (pintype "output"))
    )
    (net (code "63") (name "unconnected-(IC4-RESET#-Pad19)") (class "Default")
      (node (ref "IC4") (pin "19") (pinfunction "RESET#_19") (pintype "bidirectional"))
    )
    (net (code "64") (name "unconnected-(IC4-RI#-Pad6)") (class "Default")
      (node (ref "IC4") (pin "6") (pinfunction "RI#_6") (pintype "bidirectional"))
    )
    (net (code "65") (name "unconnected-(IC4-RTS#-Pad3)") (class "Default")
      (node (ref "IC4") (pin "3") (pinfunction "RTS#_3") (pintype "output"))
    )
    (net (code "66") (name "unconnected-(J1B-4-Pad2-4)") (class "Default")
      (node (ref "J1") (pin "2-4") (pinfunction "4_2-4") (pintype "passive"))
    )
    (net (code "67") (name "unconnected-(J1B-5-Pad2-5)") (class "Default")
      (node (ref "J1") (pin "2-5") (pinfunction "5_2-5") (pintype "passive"))
    )
    (net (code "68") (name "unconnected-(J3-ID-Pad2)") (class "Default")
      (node (ref "J3") (pin "2") (pinfunction "ID_2") (pintype "bidirectional"))
    )
    (net (code "69") (name "unconnected-(RFM69W-PadDIO1)") (class "Default")
      (node (ref "RFM69W") (pin "DIO1") (pinfunction "DIO1_DIO1") (pintype "bidirectional"))
    )
    (net (code "70") (name "unconnected-(RFM69W-PadDIO2)") (class "Default")
      (node (ref "RFM69W") (pin "DIO2") (pinfunction "DIO2_DIO2") (pintype "bidirectional"))
    )
    (net (code "71") (name "unconnected-(RFM69W-PadDIO3)") (class "Default")
      (node (ref "RFM69W") (pin "DIO3") (pinfunction "DIO3_DIO3") (pintype "bidirectional"))
    )
    (net (code "72") (name "unconnected-(RFM69W-PadDIO4)") (class "Default")
      (node (ref "RFM69W") (pin "DIO4") (pinfunction "DIO4_DIO4") (pintype "bidirectional"))
    )
    (net (code "73") (name "unconnected-(RFM69W-PadDIO5)") (class "Default")
      (node (ref "RFM69W") (pin "DIO5") (pinfunction "DIO5_DIO5") (pintype "bidirectional"))
    )
    (net (code "74") (name "unconnected-(RFM69W-PadNC)") (class "Default")
      (node (ref "RFM69W") (pin "NC") (pinfunction "NC_NC") (pintype "bidirectional"))
    )
    (net (code "75") (name "unconnected-(RFM69W-PadRESET)") (class "Default")
      (node (ref "RFM69W") (pin "RESET") (pinfunction "RESET_RESET") (pintype "bidirectional"))
    )
    (net (code "76") (name "unconnected-(U$3-PadRING_SW)") (class "Default")
      (node (ref "U$3") (pin "RING_SW") (pinfunction "RING_SW_RING_SW") (pintype "bidirectional"))
    )
    (net (code "77") (name "unconnected-(U1-PadDIO1)") (class "Default")
      (node (ref "U1") (pin "DIO1") (pinfunction "DIO1_DIO1") (pintype "bidirectional"))
    )
    (net (code "78") (name "unconnected-(U1-PadDIO2)") (class "Default")
      (node (ref "U1") (pin "DIO2") (pinfunction "DIO2_DIO2") (pintype "bidirectional"))
    )
    (net (code "79") (name "unconnected-(U1-PadRESET)") (class "Default")
      (node (ref "U1") (pin "RESET") (pinfunction "RESET_RESET") (pintype "input"))
    )
  )
)
